# CPU_ROM.net
KiCad netlist of a schematic drawn in Altium Designer
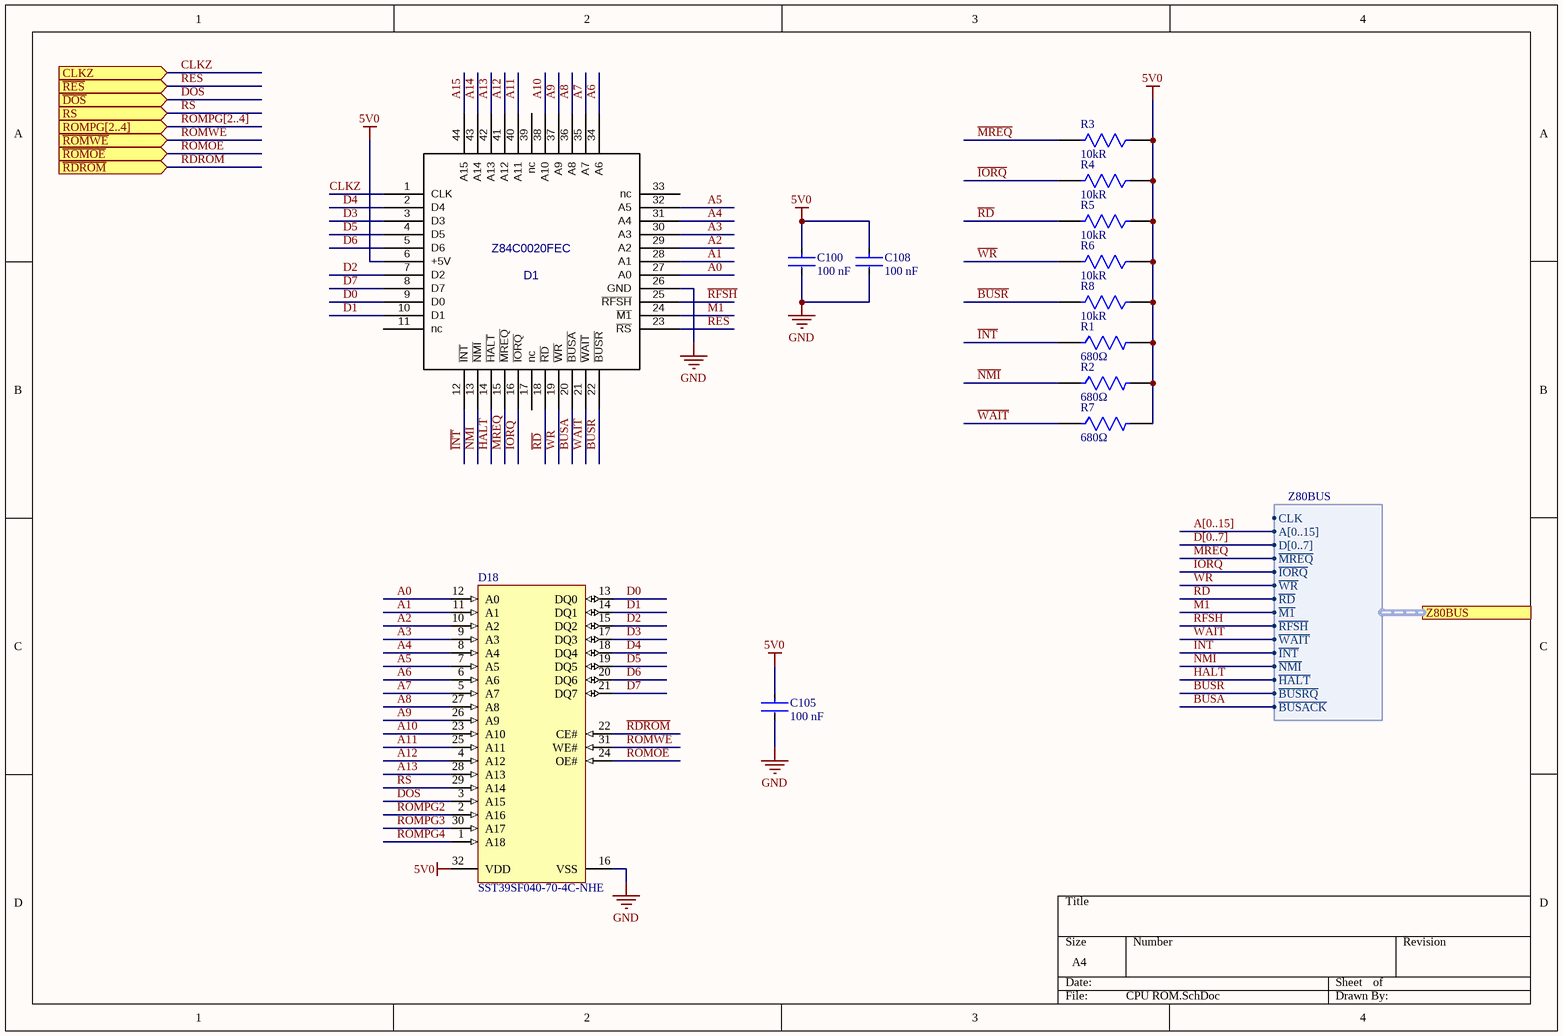
[diagram p0: CPU ROM.SchDoc]

(export (version "E")
  (design (tool "Eeschema 10.0.6"))
  (components
    (comp (ref "C100")
      (value "CC0805KRX7R9BB104")
      (footprint "FP-CC0805-0_85-IPC_A")
      (description "CAP CER 0.1UF 50V X7R 0805")
      (fields (field (name "CAPACITANCE") "100 nF") (field (name "MANUFACTURER") "Yageo"))
      (libsource (lib "SchLib") (part "CMP-2100-03606-3"))
    )
    (comp (ref "C105")
      (value "CC0805KRX7R9BB104")
      (footprint "FP-CC0805-0_85-IPC_A")
      (description "CAP CER 0.1UF 50V X7R 0805")
      (fields (field (name "CAPACITANCE") "100 nF") (field (name "MANUFACTURER") "Yageo"))
      (libsource (lib "SchLib") (part "CMP-2100-03606-3"))
    )
    (comp (ref "C108")
      (value "CC0805KRX7R9BB104")
      (footprint "FP-CC0805-0_85-IPC_A")
      (description "CAP CER 0.1UF 50V X7R 0805")
      (fields (field (name "CAPACITANCE") "100 nF") (field (name "MANUFACTURER") "Yageo"))
      (libsource (lib "SchLib") (part "CMP-2100-03606-3"))
    )
    (comp (ref "D1")
      (value "Z84C0020FEC")
      (footprint "QFP44X8")
      (libsource (lib "SchLib") (part "Z84C0020FEC"))
    )
    (comp (ref "D18")
      (value "SST39SF040-70-4C-NHE")
      (footprint "MCHP-PLCC-NH32_L")
      (description "4 Mbit Multi-Purpose Flash, 4.5 to 5.5 V, 1 kHz, 0 to 70 degC, 32-pin PLCC (NH32), Tube")
      (fields (field (name "MANUFACTURER") "Microchip"))
      (libsource (lib "SchLib") (part "CMP-0378-00006-1"))
    )
    (comp (ref "R1")
      (value "680Ω")
      (footprint "FP-RT0805-IPC_A")
      (description "RES SMD 680 OHM 1% 1/8W 0805")
      (fields
        (field (name "MANUFACTURER") "Yageo")
        (field (name "MANUFACTURER PART NUMBER") "RT0805FRE07680RL")
      )
      (libsource (lib "SchLib") (part "CMP-03412-000082-1"))
    )
    (comp (ref "R2")
      (value "680Ω")
      (footprint "FP-RT0805-IPC_A")
      (description "RES SMD 680 OHM 1% 1/8W 0805")
      (fields
        (field (name "MANUFACTURER") "Yageo")
        (field (name "MANUFACTURER PART NUMBER") "RT0805FRE07680RL")
      )
      (libsource (lib "SchLib") (part "CMP-03412-000082-1"))
    )
    (comp (ref "R3")
      (value "CR0805-JW-103ELF")
      (footprint "FP-CR0805-IPC_A")
      (description "Thick Film Chip Resistors 0805 10kΩ 0.125W 5% 200ppm/°C")
      (fields (field (name "RESISTANCE") "10kR") (field (name "MANUFACTURER") "Bourns"))
      (libsource (lib "SchLib") (part "CMP-07231-003873-1"))
    )
    (comp (ref "R4")
      (value "CR0805-JW-103ELF")
      (footprint "FP-CR0805-IPC_A")
      (description "Thick Film Chip Resistors 0805 10kΩ 0.125W 5% 200ppm/°C")
      (fields (field (name "RESISTANCE") "10kR") (field (name "MANUFACTURER") "Bourns"))
      (libsource (lib "SchLib") (part "CMP-07231-003873-1"))
    )
    (comp (ref "R5")
      (value "CR0805-JW-103ELF")
      (footprint "FP-CR0805-IPC_A")
      (description "Thick Film Chip Resistors 0805 10kΩ 0.125W 5% 200ppm/°C")
      (fields (field (name "RESISTANCE") "10kR") (field (name "MANUFACTURER") "Bourns"))
      (libsource (lib "SchLib") (part "CMP-07231-003873-1"))
    )
    (comp (ref "R6")
      (value "CR0805-JW-103ELF")
      (footprint "FP-CR0805-IPC_A")
      (description "Thick Film Chip Resistors 0805 10kΩ 0.125W 5% 200ppm/°C")
      (fields (field (name "RESISTANCE") "10kR") (field (name "MANUFACTURER") "Bourns"))
      (libsource (lib "SchLib") (part "CMP-07231-003873-1"))
    )
    (comp (ref "R7")
      (value "680Ω")
      (footprint "FP-RT0805-IPC_A")
      (description "RES SMD 680 OHM 1% 1/8W 0805")
      (fields
        (field (name "MANUFACTURER") "Yageo")
        (field (name "MANUFACTURER PART NUMBER") "RT0805FRE07680RL")
      )
      (libsource (lib "SchLib") (part "CMP-03412-000082-1"))
    )
    (comp (ref "R8")
      (value "CR0805-JW-103ELF")
      (footprint "FP-CR0805-IPC_A")
      (description "Thick Film Chip Resistors 0805 10kΩ 0.125W 5% 200ppm/°C")
      (fields (field (name "RESISTANCE") "10kR") (field (name "MANUFACTURER") "Bourns"))
      (libsource (lib "SchLib") (part "CMP-07231-003873-1"))
    )
  )
  (nets
    (net (code "2") (name "/A0") (class "Default")
      (node (ref "D1") (pin "27") (pinfunction "A0_27") (pintype "passive"))
      (node (ref "D18") (pin "12") (pinfunction "A0_12") (pintype "input"))
    )
    (net (code "3") (name "/A1") (class "Default")
      (node (ref "D1") (pin "28") (pinfunction "A1_28") (pintype "passive"))
      (node (ref "D18") (pin "11") (pinfunction "A1_11") (pintype "input"))
    )
    (net (code "4") (name "/A2") (class "Default")
      (node (ref "D1") (pin "29") (pinfunction "A2_29") (pintype "passive"))
      (node (ref "D18") (pin "10") (pinfunction "A2_10") (pintype "input"))
    )
    (net (code "5") (name "/A3") (class "Default")
      (node (ref "D1") (pin "30") (pinfunction "A3_30") (pintype "passive"))
      (node (ref "D18") (pin "9") (pinfunction "A3_9") (pintype "input"))
    )
    (net (code "6") (name "/A4") (class "Default")
      (node (ref "D1") (pin "31") (pinfunction "A4_31") (pintype "passive"))
      (node (ref "D18") (pin "8") (pinfunction "A4_8") (pintype "input"))
    )
    (net (code "7") (name "/A5") (class "Default")
      (node (ref "D1") (pin "32") (pinfunction "A5_32") (pintype "passive"))
      (node (ref "D18") (pin "7") (pinfunction "A5_7") (pintype "input"))
    )
    (net (code "8") (name "/A6") (class "Default")
      (node (ref "D1") (pin "34") (pinfunction "A6_34") (pintype "passive"))
      (node (ref "D18") (pin "6") (pinfunction "A6_6") (pintype "input"))
    )
    (net (code "9") (name "/A7") (class "Default")
      (node (ref "D1") (pin "35") (pinfunction "A7_35") (pintype "passive"))
      (node (ref "D18") (pin "5") (pinfunction "A7_5") (pintype "input"))
    )
    (net (code "10") (name "/A8") (class "Default")
      (node (ref "D1") (pin "36") (pinfunction "A8_36") (pintype "passive"))
      (node (ref "D18") (pin "27") (pinfunction "A8_27") (pintype "input"))
    )
    (net (code "11") (name "/A9") (class "Default")
      (node (ref "D1") (pin "37") (pinfunction "A9_37") (pintype "passive"))
      (node (ref "D18") (pin "26") (pinfunction "A9_26") (pintype "input"))
    )
    (net (code "12") (name "/A10") (class "Default")
      (node (ref "D1") (pin "38") (pinfunction "A10_38") (pintype "passive"))
      (node (ref "D18") (pin "23") (pinfunction "A10_23") (pintype "input"))
    )
    (net (code "13") (name "/A11") (class "Default")
      (node (ref "D1") (pin "40") (pinfunction "A11_40") (pintype "passive"))
      (node (ref "D18") (pin "25") (pinfunction "A11_25") (pintype "input"))
    )
    (net (code "14") (name "/A12") (class "Default")
      (node (ref "D1") (pin "41") (pinfunction "A12_41") (pintype "passive"))
      (node (ref "D18") (pin "4") (pinfunction "A12_4") (pintype "input"))
    )
    (net (code "15") (name "/A13") (class "Default")
      (node (ref "D1") (pin "42") (pinfunction "A13_42") (pintype "passive"))
      (node (ref "D18") (pin "28") (pinfunction "A13_28") (pintype "input"))
    )
    (net (code "16") (name "/A14") (class "Default")
      (node (ref "D1") (pin "43") (pinfunction "A14_43") (pintype "passive"))
    )
    (net (code "17") (name "/A15") (class "Default")
      (node (ref "D1") (pin "44") (pinfunction "A15_44") (pintype "passive"))
    )
    (net (code "19") (name "/CLKZ") (class "Default")
      (node (ref "D1") (pin "1") (pinfunction "CLK_1") (pintype "passive"))
    )
    (net (code "20") (name "/D0") (class "Default")
      (node (ref "D1") (pin "9") (pinfunction "D0_9") (pintype "passive"))
      (node (ref "D18") (pin "13") (pinfunction "DQ0_13") (pintype "bidirectional"))
    )
    (net (code "21") (name "/D1") (class "Default")
      (node (ref "D1") (pin "10") (pinfunction "D1_10") (pintype "passive"))
      (node (ref "D18") (pin "14") (pinfunction "DQ1_14") (pintype "bidirectional"))
    )
    (net (code "22") (name "/D2") (class "Default")
      (node (ref "D1") (pin "7") (pinfunction "D2_7") (pintype "passive"))
      (node (ref "D18") (pin "15") (pinfunction "DQ2_15") (pintype "bidirectional"))
    )
    (net (code "23") (name "/D3") (class "Default")
      (node (ref "D1") (pin "3") (pinfunction "D3_3") (pintype "passive"))
      (node (ref "D18") (pin "17") (pinfunction "DQ3_17") (pintype "bidirectional"))
    )
    (net (code "24") (name "/D4") (class "Default")
      (node (ref "D1") (pin "2") (pinfunction "D4_2") (pintype "passive"))
      (node (ref "D18") (pin "18") (pinfunction "DQ4_18") (pintype "bidirectional"))
    )
    (net (code "25") (name "/D5") (class "Default")
      (node (ref "D1") (pin "4") (pinfunction "D5_4") (pintype "passive"))
      (node (ref "D18") (pin "19") (pinfunction "DQ5_19") (pintype "bidirectional"))
    )
    (net (code "26") (name "/D6") (class "Default")
      (node (ref "D1") (pin "5") (pinfunction "D6_5") (pintype "passive"))
      (node (ref "D18") (pin "20") (pinfunction "DQ6_20") (pintype "bidirectional"))
    )
    (net (code "27") (name "/D7") (class "Default")
      (node (ref "D1") (pin "8") (pinfunction "D7_8") (pintype "passive"))
      (node (ref "D18") (pin "21") (pinfunction "DQ7_21") (pintype "bidirectional"))
    )
    (net (code "28") (name "/ROMPG2") (class "Default")
      (node (ref "D18") (pin "2") (pinfunction "A16_2") (pintype "input"))
    )
    (net (code "29") (name "/ROMPG3") (class "Default")
      (node (ref "D18") (pin "30") (pinfunction "A17_30") (pintype "input"))
    )
    (net (code "30") (name "/ROMPG4") (class "Default")
      (node (ref "D18") (pin "1") (pinfunction "A18_1") (pintype "input"))
    )
    (net (code "32") (name "/RS") (class "Default")
      (node (ref "D18") (pin "29") (pinfunction "A14_29") (pintype "input"))
    )
    (net (code "35") (name "/~{BUSA}") (class "Default")
      (node (ref "D1") (pin "20") (pinfunction "~{BUSA}_20") (pintype "passive"))
    )
    (net (code "36") (name "/~{BUSR}") (class "Default")
      (node (ref "D1") (pin "22") (pinfunction "~{BUSR}_22") (pintype "passive"))
      (node (ref "R8") (pin "2") (pinfunction "2_2") (pintype "passive"))
    )
    (net (code "37") (name "/~{DOS}") (class "Default")
      (node (ref "D18") (pin "3") (pinfunction "A15_3") (pintype "input"))
    )
    (net (code "38") (name "/~{HALT}") (class "Default")
      (node (ref "D1") (pin "14") (pinfunction "~{HALT}_14") (pintype "passive"))
    )
    (net (code "39") (name "/~{INT}") (class "Default")
      (node (ref "D1") (pin "12") (pinfunction "~{INT}_12") (pintype "passive"))
      (node (ref "R1") (pin "1") (pinfunction "1_1") (pintype "passive"))
    )
    (net (code "40") (name "/~{IORQ}") (class "Default")
      (node (ref "D1") (pin "16") (pinfunction "~{IORQ}_16") (pintype "passive"))
      (node (ref "R4") (pin "2") (pinfunction "2_2") (pintype "passive"))
    )
    (net (code "41") (name "/~{M1}") (class "Default")
      (node (ref "D1") (pin "24") (pinfunction "~{M1}_24") (pintype "passive"))
    )
    (net (code "42") (name "/~{MREQ}") (class "Default")
      (node (ref "D1") (pin "15") (pinfunction "~{MREQ}_15") (pintype "passive"))
      (node (ref "R3") (pin "2") (pinfunction "2_2") (pintype "passive"))
    )
    (net (code "43") (name "/~{NMI}") (class "Default")
      (node (ref "D1") (pin "13") (pinfunction "~{NMI}_13") (pintype "passive"))
      (node (ref "R2") (pin "1") (pinfunction "1_1") (pintype "passive"))
    )
    (net (code "44") (name "/~{RDROM}") (class "Default")
      (node (ref "D18") (pin "22") (pinfunction "CE#_22") (pintype "input"))
    )
    (net (code "45") (name "/~{RD}") (class "Default")
      (node (ref "D1") (pin "18") (pinfunction "~{RD}_18") (pintype "passive"))
      (node (ref "R5") (pin "2") (pinfunction "2_2") (pintype "passive"))
    )
    (net (code "46") (name "/~{RES}") (class "Default")
      (node (ref "D1") (pin "23") (pinfunction "~{RS}_23") (pintype "passive"))
    )
    (net (code "47") (name "/~{RFSH}") (class "Default")
      (node (ref "D1") (pin "25") (pinfunction "~{RFSH}_25") (pintype "passive"))
    )
    (net (code "48") (name "/~{ROMOE}") (class "Default")
      (node (ref "D18") (pin "24") (pinfunction "OE#_24") (pintype "input"))
    )
    (net (code "49") (name "/~{ROMWE}") (class "Default")
      (node (ref "D18") (pin "31") (pinfunction "WE#_31") (pintype "input"))
    )
    (net (code "50") (name "/~{WAIT}") (class "Default")
      (node (ref "D1") (pin "21") (pinfunction "~{WAIT}_21") (pintype "passive"))
      (node (ref "R7") (pin "1") (pinfunction "1_1") (pintype "passive"))
    )
    (net (code "51") (name "/~{WR}") (class "Default")
      (node (ref "D1") (pin "19") (pinfunction "~{WR}_19") (pintype "passive"))
      (node (ref "R6") (pin "2") (pinfunction "2_2") (pintype "passive"))
    )
    (net (code "52") (name "5V0") (class "Default")
      (node (ref "C100") (pin "1") (pinfunction "1_1") (pintype "passive"))
      (node (ref "C105") (pin "1") (pinfunction "1_1") (pintype "passive"))
      (node (ref "C108") (pin "1") (pinfunction "1_1") (pintype "passive"))
      (node (ref "D1") (pin "6") (pinfunction "+5V_6") (pintype "passive"))
      (node (ref "D18") (pin "32") (pinfunction "VDD_32") (pintype "power_in"))
      (node (ref "R1") (pin "2") (pinfunction "2_2") (pintype "passive"))
      (node (ref "R2") (pin "2") (pinfunction "2_2") (pintype "passive"))
      (node (ref "R3") (pin "1") (pinfunction "1_1") (pintype "passive"))
      (node (ref "R4") (pin "1") (pinfunction "1_1") (pintype "passive"))
      (node (ref "R5") (pin "1") (pinfunction "1_1") (pintype "passive"))
      (node (ref "R6") (pin "1") (pinfunction "1_1") (pintype "passive"))
      (node (ref "R7") (pin "2") (pinfunction "2_2") (pintype "passive"))
      (node (ref "R8") (pin "1") (pinfunction "1_1") (pintype "passive"))
    )
    (net (code "53") (name "GND") (class "Default")
      (node (ref "C100") (pin "2") (pinfunction "2_2") (pintype "passive"))
      (node (ref "C105") (pin "2") (pinfunction "2_2") (pintype "passive"))
      (node (ref "C108") (pin "2") (pinfunction "2_2") (pintype "passive"))
      (node (ref "D1") (pin "26") (pinfunction "GND_26") (pintype "passive"))
      (node (ref "D18") (pin "16") (pinfunction "VSS_16") (pintype "power_in"))
    )
    (net (code "54") (name "unconnected-(D1-nc-Pad11)") (class "Default")
      (node (ref "D1") (pin "11") (pinfunction "nc_11") (pintype "passive"))
    )
    (net (code "55") (name "unconnected-(D1-nc-Pad17)") (class "Default")
      (node (ref "D1") (pin "17") (pinfunction "nc_17") (pintype "passive"))
    )
    (net (code "56") (name "unconnected-(D1-nc-Pad33)") (class "Default")
      (node (ref "D1") (pin "33") (pinfunction "nc_33") (pintype "passive"))
    )
    (net (code "57") (name "unconnected-(D1-nc-Pad39)") (class "Default")
      (node (ref "D1") (pin "39") (pinfunction "nc_39") (pintype "passive"))
    )
  )
)
